# 3V3.net
KiCad netlist of a schematic drawn in Altium Designer
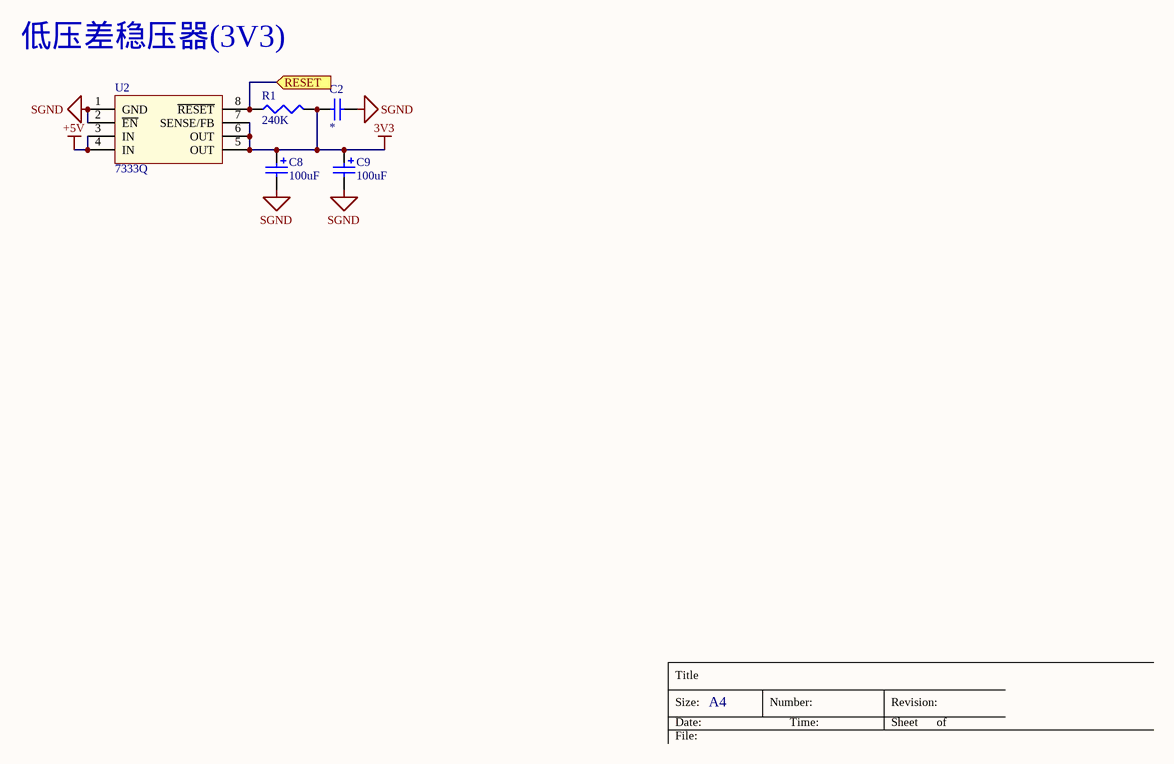
[diagram p0: 3V3低压模块.SchDoc]

(export (version "E")
  (design (tool "Eeschema 10.0.6"))
  (components
    (comp (ref "C2")
      (value "Cap")
      (footprint "0603-L")
      (description "Capacitor")
      (fields (field (name "ALTIUM_VALUE") "*") (field (name "PUBLISHER") "Altium Limited"))
      (libsource (lib "Miscellaneous Devices") (part "Cap"))
    )
    (comp (ref "C8")
      (value "100uF")
      (footprint "CAP1+")
      (description "Polarized Capacitor (Axial)")
      (fields (field (name "Comment") "Cap Pol2") (field (name "PUBLISHER") "Altium Limited"))
      (libsource (lib "Miscellaneous Devices") (part "Cap Pol2"))
    )
    (comp (ref "C9")
      (value "100uF")
      (footprint "CAP1+")
      (description "Polarized Capacitor (Axial)")
      (fields (field (name "Comment") "Cap Pol2") (field (name "PUBLISHER") "Altium Limited"))
      (libsource (lib "Miscellaneous Devices") (part "Cap Pol2"))
    )
    (comp (ref "R1")
      (value "240K")
      (footprint "0805")
      (description "Resistor")
      (fields (field (name "Comment") "Res3") (field (name "PUBLISHER") "Altium Limited"))
      (libsource (lib "Miscellaneous Devices") (part "Res3"))
    )
    (comp (ref "U2")
      (value "7333Q")
      (footprint "TJA10")
      (description "3.3V Output voltage")
      (libsource (lib "整车控制器") (part "7333Q"))
    )
  )
  (nets
    (net (code "1") (name "+5V") (class "Default")
      (node (ref "U2") (pin "3") (pinfunction "IN_3") (pintype "passive"))
      (node (ref "U2") (pin "4") (pinfunction "IN_4") (pintype "passive"))
    )
    (net (code "2") (name "/RESET") (class "Default")
      (node (ref "R1") (pin "1") (pinfunction "1_1") (pintype "passive"))
      (node (ref "U2") (pin "8") (pinfunction "~{RESET}_8") (pintype "passive"))
    )
    (net (code "3") (name "3V3") (class "Default")
      (node (ref "C2") (pin "2") (pinfunction "2_2") (pintype "passive"))
      (node (ref "C8") (pin "1") (pinfunction "1_1") (pintype "passive"))
      (node (ref "C9") (pin "1") (pinfunction "1_1") (pintype "passive"))
      (node (ref "R1") (pin "2") (pinfunction "2_2") (pintype "passive"))
      (node (ref "U2") (pin "5") (pinfunction "OUT_5") (pintype "passive"))
      (node (ref "U2") (pin "6") (pinfunction "OUT_6") (pintype "passive"))
      (node (ref "U2") (pin "7") (pinfunction "SENSE/FB_7") (pintype "passive"))
    )
    (net (code "4") (name "SGND") (class "Default")
      (node (ref "C2") (pin "1") (pinfunction "1_1") (pintype "passive"))
      (node (ref "C8") (pin "2") (pinfunction "2_2") (pintype "passive"))
      (node (ref "C9") (pin "2") (pinfunction "2_2") (pintype "passive"))
      (node (ref "U2") (pin "1") (pinfunction "GND_1") (pintype "passive"))
      (node (ref "U2") (pin "2") (pinfunction "~{EN}_2") (pintype "passive"))
    )
  )
)
